# Sheet2.net
KiCad netlist of a schematic drawn in Altium Designer
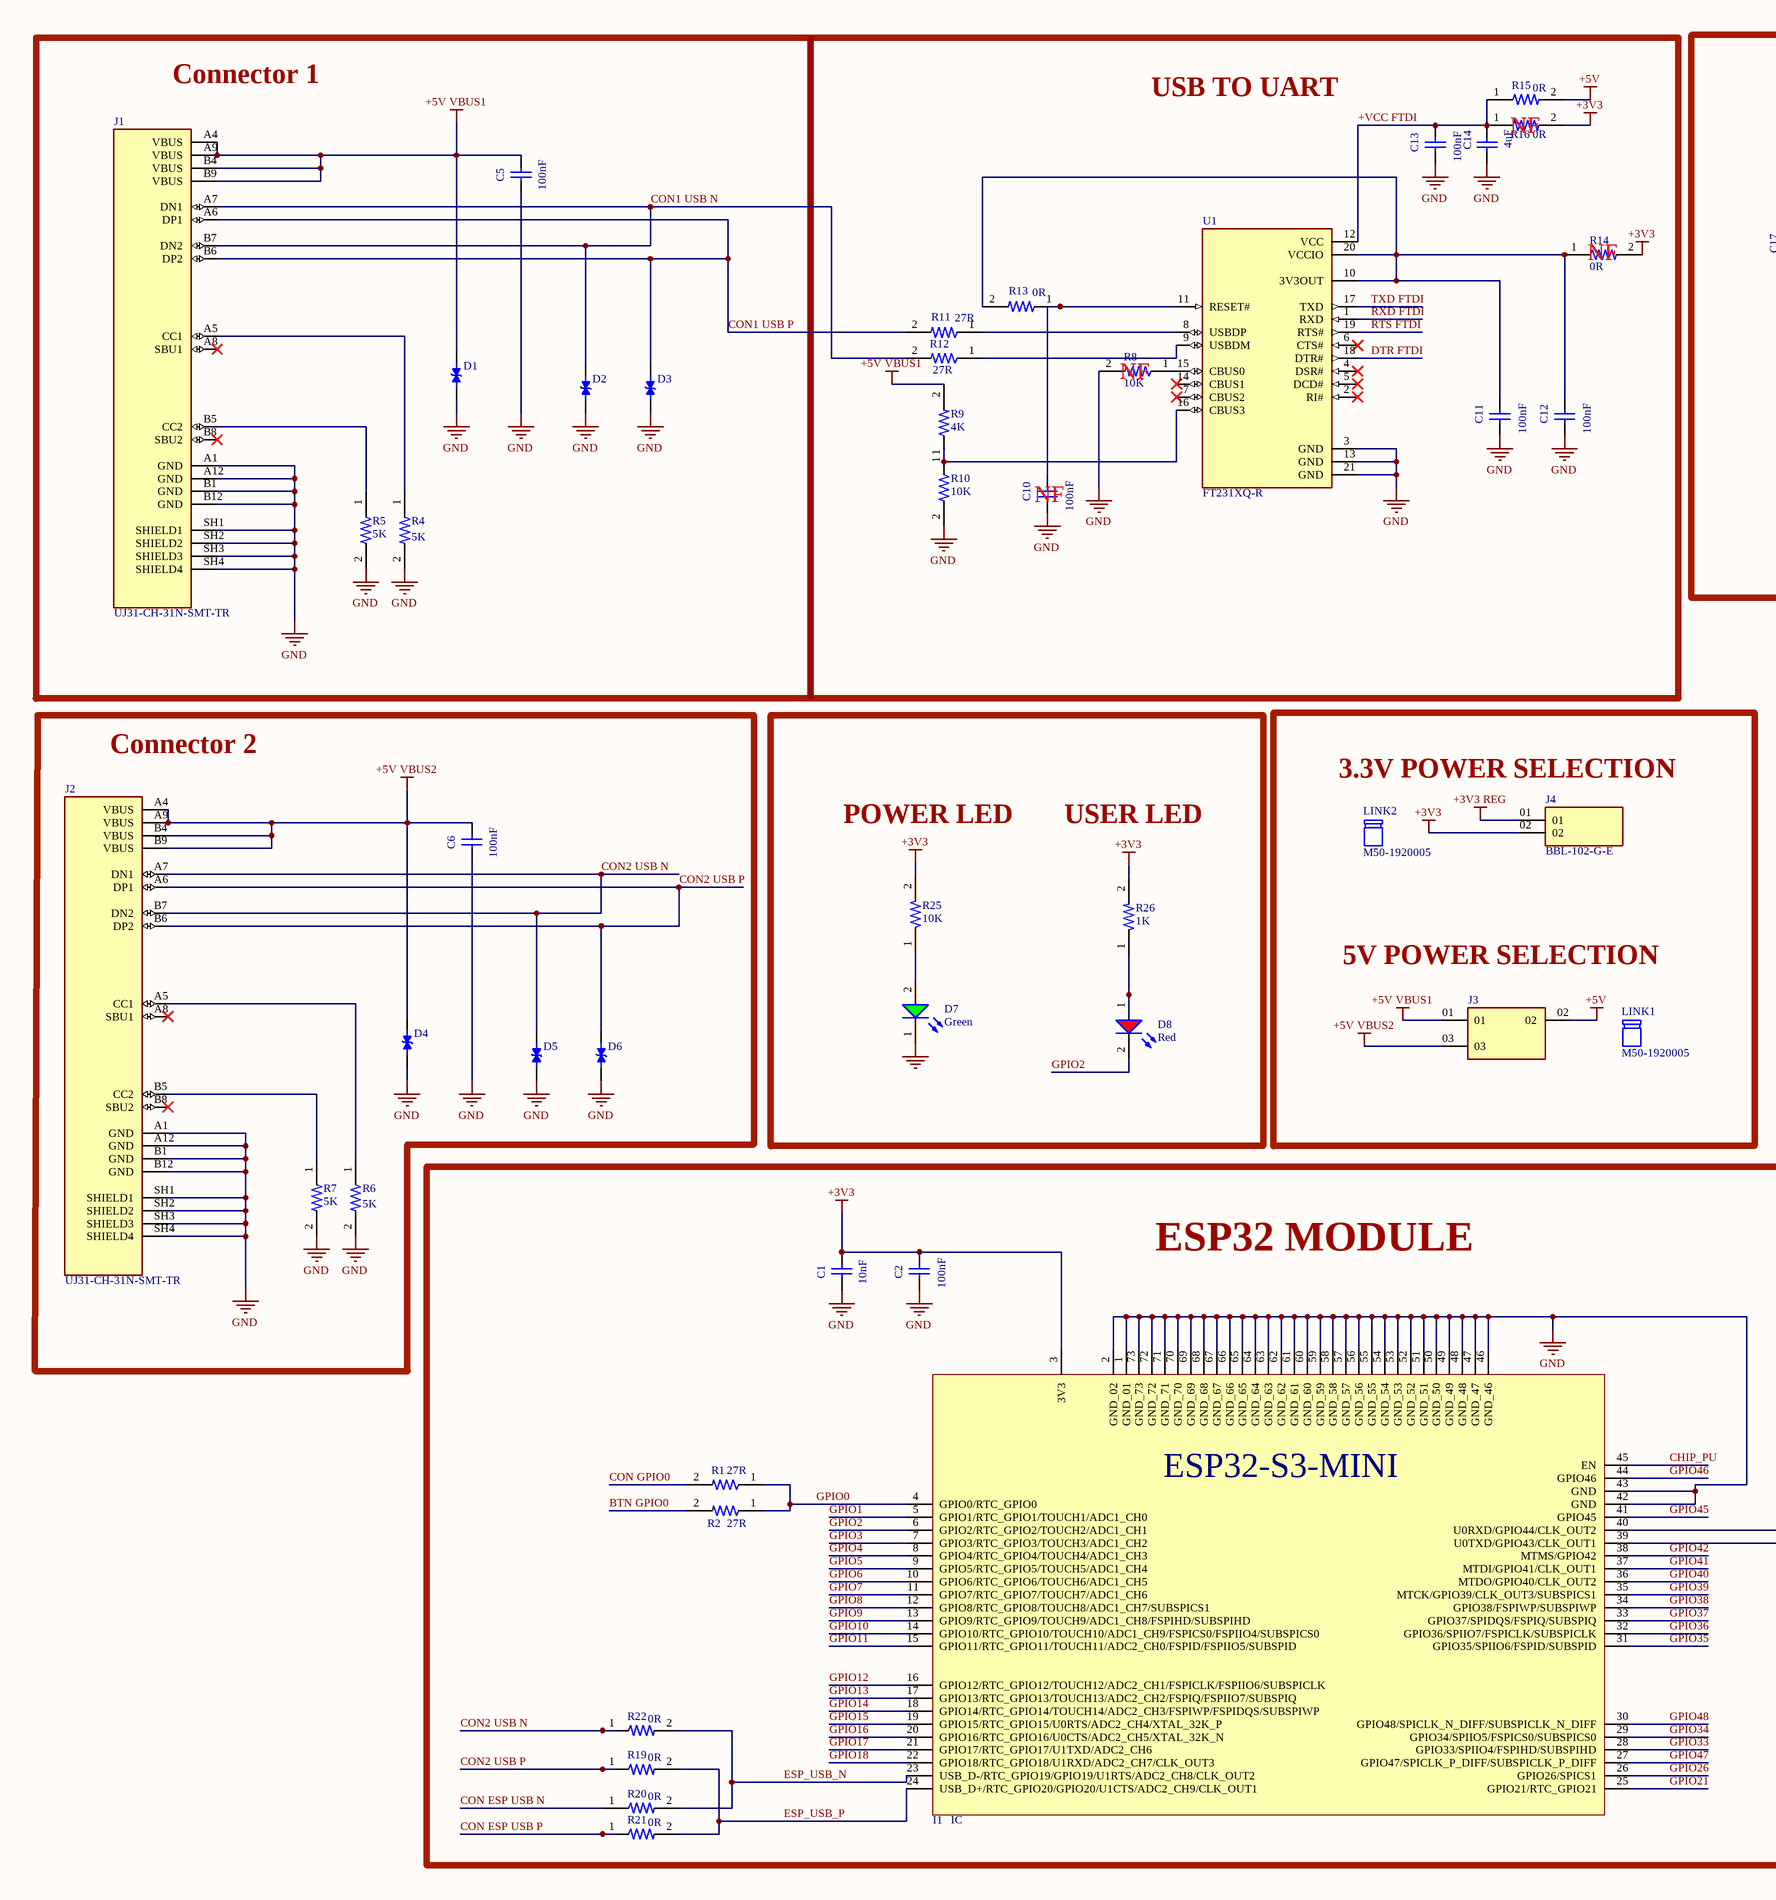
[diagram p0: Sheet2.SchDoc, left]
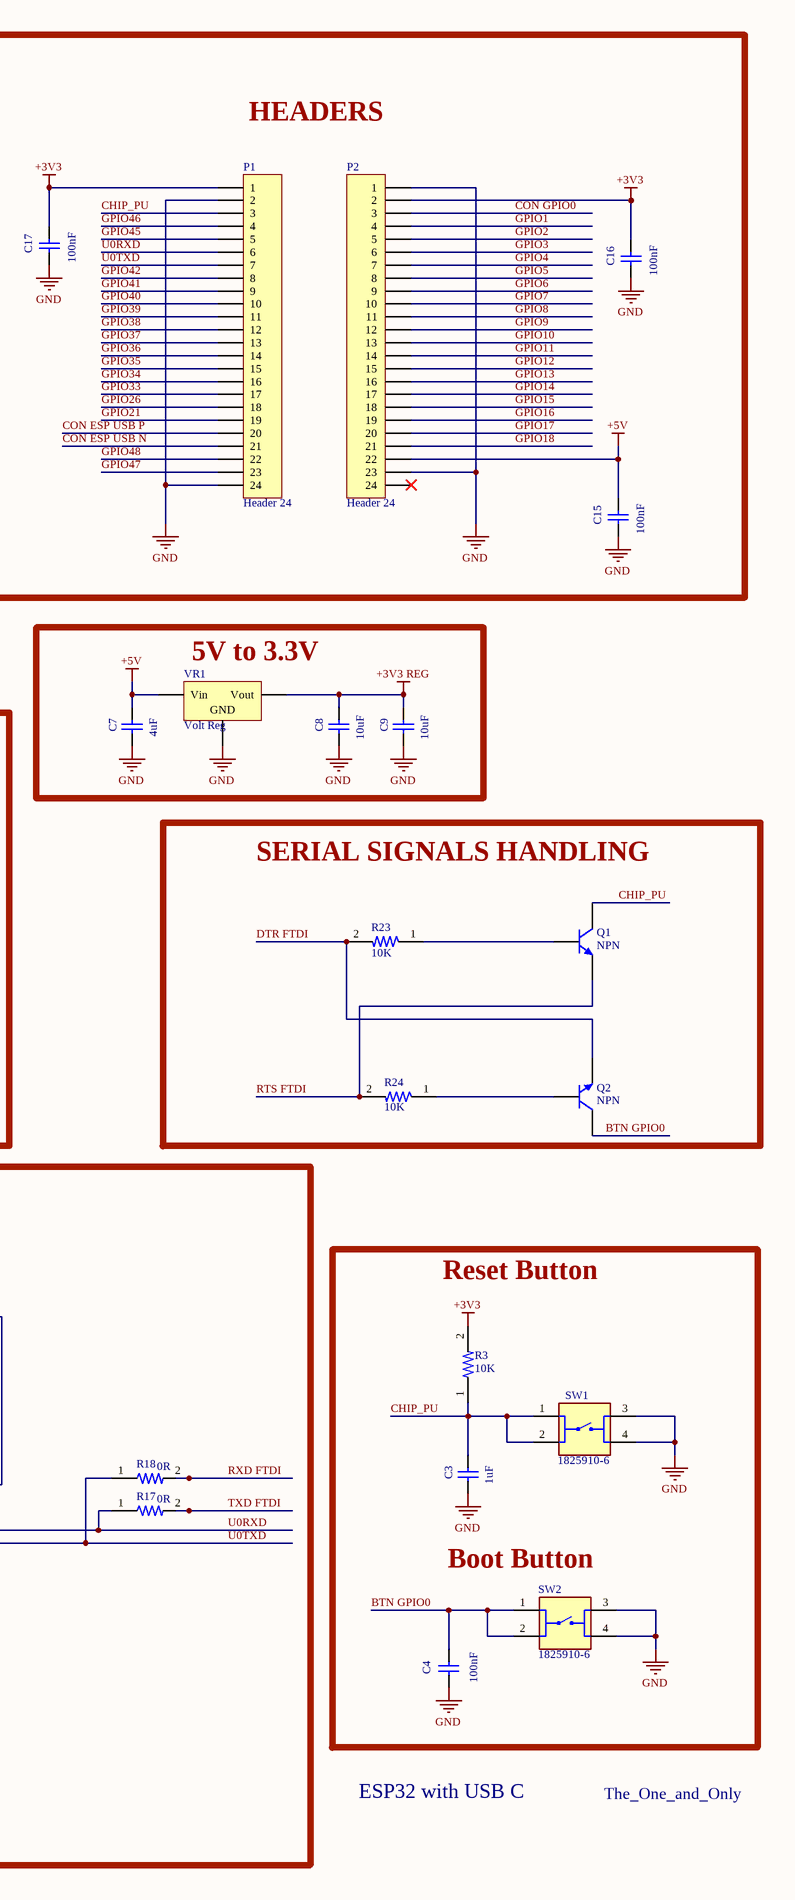
[diagram p1: Sheet2.SchDoc, right]

(export (version "E")
  (design (tool "Eeschema 10.0.6"))
  (components
    (comp (ref "C1")
      (value "10nF")
      (footprint "WCAP-CSGP_0603_L1.6W0.8H0.8_Reflow")
      (description "WCAP-CSGP Multilayer Ceramic Chip Capacitor, General Purpose, size 0603, X5R, 2.2μF, 16V")
      (fields
        (field (name "MANUFACTURER PART NUMBER") "885012106029")
        (field (name "MANUFACTURER") "Wurth Elektronik")
      )
      (libsource (lib "885012004001_Altium_WCAP-CSGP_rev24c") (part "885012106029"))
    )
    (comp (ref "C2")
      (value "100nF")
      (footprint "WCAP-CSGP_0603_L1.6W0.8H0.8_Reflow")
      (description "WCAP-CSGP Multilayer Ceramic Chip Capacitor, General Purpose, size 0603, X5R, 2.2μF, 16V")
      (fields
        (field (name "MANUFACTURER PART NUMBER") "885012106029")
        (field (name "MANUFACTURER") "Wurth Elektronik")
      )
      (libsource (lib "885012004001_Altium_WCAP-CSGP_rev24c") (part "885012106029"))
    )
    (comp (ref "C3")
      (value "1uF")
      (footprint "WCAP-CSGP_0603_L1.6W0.8H0.8_Reflow")
      (description "WCAP-CSGP Multilayer Ceramic Chip Capacitor, General Purpose, size 0603, X5R, 2.2μF, 16V")
      (fields
        (field (name "MANUFACTURER PART NUMBER") "885012106029")
        (field (name "MANUFACTURER") "Wurth Elektronik")
      )
      (libsource (lib "885012004001_Altium_WCAP-CSGP_rev24c") (part "885012106029"))
    )
    (comp (ref "C4")
      (value "100nF")
      (footprint "WCAP-CSGP_0603_L1.6W0.8H0.8_Reflow")
      (description "WCAP-CSGP Multilayer Ceramic Chip Capacitor, General Purpose, size 0603, X5R, 2.2μF, 16V")
      (fields
        (field (name "MANUFACTURER PART NUMBER") "885012106029")
        (field (name "MANUFACTURER") "Wurth Elektronik")
      )
      (libsource (lib "885012004001_Altium_WCAP-CSGP_rev24c") (part "885012106029"))
    )
    (comp (ref "C5")
      (value "100nF")
      (footprint "WCAP-CSGP_0603_L1.6W0.8H0.8_Reflow")
      (description "WCAP-CSGP Multilayer Ceramic Chip Capacitor, General Purpose, size 0603, X5R, 2.2μF, 16V")
      (fields
        (field (name "MANUFACTURER PART NUMBER") "885012106029")
        (field (name "MANUFACTURER") "Wurth Elektronik")
      )
      (libsource (lib "885012004001_Altium_WCAP-CSGP_rev24c") (part "885012106029"))
    )
    (comp (ref "C6")
      (value "100nF")
      (footprint "WCAP-CSGP_0603_L1.6W0.8H0.8_Reflow")
      (description "WCAP-CSGP Multilayer Ceramic Chip Capacitor, General Purpose, size 0603, X5R, 2.2μF, 16V")
      (fields
        (field (name "MANUFACTURER PART NUMBER") "885012106029")
        (field (name "MANUFACTURER") "Wurth Elektronik")
      )
      (libsource (lib "885012004001_Altium_WCAP-CSGP_rev24c") (part "885012106029"))
    )
    (comp (ref "C7")
      (value "4uF")
      (footprint "WCAP-CSGP_0603_L1.6W0.8H0.8_Reflow")
      (description "WCAP-CSGP Multilayer Ceramic Chip Capacitor, General Purpose, size 0603, X5R, 2.2μF, 16V")
      (fields
        (field (name "MANUFACTURER PART NUMBER") "885012106029")
        (field (name "MANUFACTURER") "Wurth Elektronik")
      )
      (libsource (lib "885012004001_Altium_WCAP-CSGP_rev24c") (part "885012106029"))
    )
    (comp (ref "C8")
      (value "10uF")
      (footprint "WCAP-CSGP_0603_L1.6W0.8H0.8_Reflow")
      (description "WCAP-CSGP Multilayer Ceramic Chip Capacitor, General Purpose, size 0603, X5R, 2.2μF, 16V")
      (fields
        (field (name "MANUFACTURER PART NUMBER") "885012106029")
        (field (name "MANUFACTURER") "Wurth Elektronik")
      )
      (libsource (lib "885012004001_Altium_WCAP-CSGP_rev24c") (part "885012106029"))
    )
    (comp (ref "C9")
      (value "10uF")
      (footprint "WCAP-CSGP_0603_L1.6W0.8H0.8_Reflow")
      (description "WCAP-CSGP Multilayer Ceramic Chip Capacitor, General Purpose, size 0603, X5R, 2.2μF, 16V")
      (fields
        (field (name "MANUFACTURER PART NUMBER") "885012106029")
        (field (name "MANUFACTURER") "Wurth Elektronik")
      )
      (libsource (lib "885012004001_Altium_WCAP-CSGP_rev24c") (part "885012106029"))
    )
    (comp (ref "C10")
      (value "100nF")
      (footprint "WCAP-CSGP_0603_L1.6W0.8H0.8_Reflow")
      (description "WCAP-CSGP Multilayer Ceramic Chip Capacitor, General Purpose, size 0603, X5R, 2.2μF, 16V")
      (fields
        (field (name "MANUFACTURER PART NUMBER") "885012106029")
        (field (name "MANUFACTURER") "Wurth Elektronik")
      )
      (libsource (lib "885012004001_Altium_WCAP-CSGP_rev24c") (part "885012106029"))
    )
    (comp (ref "C11")
      (value "100nF")
      (footprint "WCAP-CSGP_0603_L1.6W0.8H0.8_Reflow")
      (description "WCAP-CSGP Multilayer Ceramic Chip Capacitor, General Purpose, size 0603, X5R, 2.2μF, 16V")
      (fields
        (field (name "MANUFACTURER PART NUMBER") "885012106029")
        (field (name "MANUFACTURER") "Wurth Elektronik")
      )
      (libsource (lib "885012004001_Altium_WCAP-CSGP_rev24c") (part "885012106029"))
    )
    (comp (ref "C12")
      (value "100nF")
      (footprint "WCAP-CSGP_0603_L1.6W0.8H0.8_Reflow")
      (description "WCAP-CSGP Multilayer Ceramic Chip Capacitor, General Purpose, size 0603, X5R, 2.2μF, 16V")
      (fields
        (field (name "MANUFACTURER PART NUMBER") "885012106029")
        (field (name "MANUFACTURER") "Wurth Elektronik")
      )
      (libsource (lib "885012004001_Altium_WCAP-CSGP_rev24c") (part "885012106029"))
    )
    (comp (ref "C13")
      (value "100nF")
      (footprint "WCAP-CSGP_0603_L1.6W0.8H0.8_Reflow")
      (description "WCAP-CSGP Multilayer Ceramic Chip Capacitor, General Purpose, size 0603, X5R, 2.2μF, 16V")
      (fields
        (field (name "MANUFACTURER PART NUMBER") "885012106029")
        (field (name "MANUFACTURER") "Wurth Elektronik")
      )
      (libsource (lib "885012004001_Altium_WCAP-CSGP_rev24c") (part "885012106029"))
    )
    (comp (ref "C14")
      (value "4uF")
      (footprint "WCAP-CSGP_0603_L1.6W0.8H0.8_Reflow")
      (description "WCAP-CSGP Multilayer Ceramic Chip Capacitor, General Purpose, size 0603, X5R, 2.2μF, 16V")
      (fields
        (field (name "MANUFACTURER PART NUMBER") "885012106029")
        (field (name "MANUFACTURER") "Wurth Elektronik")
      )
      (libsource (lib "885012004001_Altium_WCAP-CSGP_rev24c") (part "885012106029"))
    )
    (comp (ref "C15")
      (value "100nF")
      (footprint "WCAP-CSGP_0603_L1.6W0.8H0.8_Reflow")
      (description "WCAP-CSGP Multilayer Ceramic Chip Capacitor, General Purpose, size 0603, X5R, 2.2μF, 16V")
      (fields
        (field (name "MANUFACTURER PART NUMBER") "885012106029")
        (field (name "MANUFACTURER") "Wurth Elektronik")
      )
      (libsource (lib "885012004001_Altium_WCAP-CSGP_rev24c") (part "885012106029"))
    )
    (comp (ref "C16")
      (value "100nF")
      (footprint "WCAP-CSGP_0603_L1.6W0.8H0.8_Reflow")
      (description "WCAP-CSGP Multilayer Ceramic Chip Capacitor, General Purpose, size 0603, X5R, 2.2μF, 16V")
      (fields
        (field (name "MANUFACTURER PART NUMBER") "885012106029")
        (field (name "MANUFACTURER") "Wurth Elektronik")
      )
      (libsource (lib "885012004001_Altium_WCAP-CSGP_rev24c") (part "885012106029"))
    )
    (comp (ref "C17")
      (value "100nF")
      (footprint "WCAP-CSGP_0603_L1.6W0.8H0.8_Reflow")
      (description "WCAP-CSGP Multilayer Ceramic Chip Capacitor, General Purpose, size 0603, X5R, 2.2μF, 16V")
      (fields
        (field (name "MANUFACTURER PART NUMBER") "885012106029")
        (field (name "MANUFACTURER") "Wurth Elektronik")
      )
      (libsource (lib "885012004001_Altium_WCAP-CSGP_rev24c") (part "885012106029"))
    )
    (comp (ref "D1")
      (value "TESDU12VRGG")
      (footprint "DIO_TESDU12VRGG")
      (description "33V Clamp 5A Ipp Tvs Diode Surface Mount 0603")
      (fields (field (name "MF") "Taiwan Semiconductor"))
      (libsource (lib "TESDU12VRGG") (part "TESDU12VRGG"))
    )
    (comp (ref "D2")
      (value "TESDU12VRGG")
      (footprint "DIO_TESDU12VRGG")
      (description "33V Clamp 5A Ipp Tvs Diode Surface Mount 0603")
      (fields (field (name "MF") "Taiwan Semiconductor"))
      (libsource (lib "TESDU12VRGG") (part "TESDU12VRGG"))
    )
    (comp (ref "D3")
      (value "TESDU12VRGG")
      (footprint "DIO_TESDU12VRGG")
      (description "33V Clamp 5A Ipp Tvs Diode Surface Mount 0603")
      (fields (field (name "MF") "Taiwan Semiconductor"))
      (libsource (lib "TESDU12VRGG") (part "TESDU12VRGG"))
    )
    (comp (ref "D4")
      (value "TESDU12VRGG")
      (footprint "DIO_TESDU12VRGG")
      (description "33V Clamp 5A Ipp Tvs Diode Surface Mount 0603")
      (fields (field (name "MF") "Taiwan Semiconductor"))
      (libsource (lib "TESDU12VRGG") (part "TESDU12VRGG"))
    )
    (comp (ref "D5")
      (value "TESDU12VRGG")
      (footprint "DIO_TESDU12VRGG")
      (description "33V Clamp 5A Ipp Tvs Diode Surface Mount 0603")
      (fields (field (name "MF") "Taiwan Semiconductor"))
      (libsource (lib "TESDU12VRGG") (part "TESDU12VRGG"))
    )
    (comp (ref "D6")
      (value "TESDU12VRGG")
      (footprint "DIO_TESDU12VRGG")
      (description "33V Clamp 5A Ipp Tvs Diode Surface Mount 0603")
      (fields (field (name "MF") "Taiwan Semiconductor"))
      (libsource (lib "TESDU12VRGG") (part "TESDU12VRGG"))
    )
    (comp (ref "D7")
      (value "Green")
      (footprint "WL-SMCW_0603_150060xx83000")
      (description "WL-SMCW Mono-color Chip LED Waterclear, SMT, size 0603, Green, 3.3V, 30°")
      (fields
        (field (name "MANUFACTURER PART NUMBER") "150060GS83000")
        (field (name "MANUFACTURER") "Wurth Elektronik")
      )
      (libsource (lib "150060AS75000_Altium_WL-SMCW_rev24b") (part "150060GS83000"))
    )
    (comp (ref "D8")
      (value "Red")
      (footprint "WL-SMCW_0603_150060xx75003")
      (description "WL-SMCW Mono-color Chip LED Waterclear, SMT, size 0603, Red, 2V, 140°")
      (fields
        (field (name "MANUFACTURER PART NUMBER") "150060RS75003")
        (field (name "MANUFACTURER") "Wurth Elektronik")
      )
      (libsource (lib "150060AS75000_Altium_WL-SMCW_rev24b") (part "150060RS75003"))
    )
    (comp (ref "I1")
      (value "IC")
      (footprint "XCVR_ESP32-MINI-1-N4")
      (libsource (lib "Schlib1") (part "Component_1"))
    )
    (comp (ref "J1")
      (value "UJ31-CH-31N-SMT-TR")
      (footprint "CUI_UJ31-CH-31N-SMT-TR")
      (description "Type C, USB 3.1 Gen 2, 5 A, Right Angle, Surface Mount (SMT), USB Receptacle")
      (fields (field (name "MF") "CUI Devices"))
      (libsource (lib "UJ31-CH-31N-SMT-TR") (part "UJ31-CH-31N-SMT-TR"))
    )
    (comp (ref "J2")
      (value "UJ31-CH-31N-SMT-TR")
      (footprint "CUI_UJ31-CH-31N-SMT-TR")
      (description "Type C, USB 3.1 Gen 2, 5 A, Right Angle, Surface Mount (SMT), USB Receptacle")
      (fields (field (name "MF") "CUI Devices"))
      (libsource (lib "UJ31-CH-31N-SMT-TR") (part "UJ31-CH-31N-SMT-TR"))
    )
    (comp (ref "J3")
      (value "TSW-101-23-S-T")
      (footprint "SAMTEC_TSW-101-23-S-T")
      (libsource (lib "TSW-101-23-S-T") (part "TSW-101-23-S-T"))
    )
    (comp (ref "J4")
      (value "BBL-102-G-E")
      (footprint "SAMTEC_BBL-102-G-E")
      (libsource (lib "BBL-102-G-E") (part "BBL-102-G-E"))
    )
    (comp (ref "LINK1")
      (value "M50-1920005")
      (description "CONN SHUNT 1.27MM RED")
      (fields (field (name "MANUFACTURER") "Harwin") (field (name "LCSC PART NUMBER") "C6985646"))
      (libsource (lib "Schlib") (part "M50-1920005"))
    )
    (comp (ref "LINK2")
      (value "M50-1920005")
      (description "CONN SHUNT 1.27MM RED")
      (fields (field (name "MANUFACTURER") "Harwin") (field (name "LCSC PART NUMBER") "C6985646"))
      (libsource (lib "Schlib") (part "M50-1920005"))
    )
    (comp (ref "P1")
      (value "Header 24")
      (footprint "HDR1X24")
      (description "Header, 24-Pin")
      (fields (field (name "PUBLISHER") "Altium Limited"))
      (libsource (lib "Miscellaneous Connectors") (part "Header 24"))
    )
    (comp (ref "P2")
      (value "Header 24")
      (footprint "HDR1X24")
      (description "Header, 24-Pin")
      (fields (field (name "PUBLISHER") "Altium Limited"))
      (libsource (lib "") (part "Header 24_1"))
    )
    (comp (ref "Q1")
      (value "NPN")
      (footprint "TO-226-AA")
      (description "NPN Bipolar Transistor")
      (fields (field (name "PUBLISHER") "Altium Limited"))
      (libsource (lib "Miscellaneous Devices") (part "NPN"))
    )
    (comp (ref "Q2")
      (value "NPN")
      (footprint "TO-226-AA")
      (description "NPN Bipolar Transistor")
      (fields (field (name "PUBLISHER") "Altium Limited"))
      (libsource (lib "Miscellaneous Devices") (part "NPN"))
    )
    (comp (ref "R1")
      (value "27R")
      (footprint "RESC1608X50N_CPF0603F10KC1")
      (description "Res Thin Film 0603 10K Ohm 1% 1/16W Â±50ppm/Â°C Molded SMD SMD Paper T/R")
      (fields (field (name "TOLERANCE") "1%") (field (name "MF") "TE Connectivity"))
      (libsource (lib "CPF0603F10KC1") (part "CPF0603F10KC1"))
    )
    (comp (ref "R2")
      (value "27R")
      (footprint "RESC1608X50N_CPF0603F10KC1")
      (description "Res Thin Film 0603 10K Ohm 1% 1/16W Â±50ppm/Â°C Molded SMD SMD Paper T/R")
      (fields (field (name "TOLERANCE") "1%") (field (name "MF") "TE Connectivity"))
      (libsource (lib "CPF0603F10KC1") (part "CPF0603F10KC1"))
    )
    (comp (ref "R3")
      (value "10K")
      (footprint "RESC1608X50N_CPF0603F10KC1")
      (description "Res Thin Film 0603 10K Ohm 1% 1/16W Â±50ppm/Â°C Molded SMD SMD Paper T/R")
      (fields (field (name "TOLERANCE") "1%") (field (name "MF") "TE Connectivity"))
      (libsource (lib "CPF0603F10KC1") (part "CPF0603F10KC1"))
    )
    (comp (ref "R4")
      (value "5K")
      (footprint "RESC1608X50N_CPF0603F10KC1")
      (description "Res Thin Film 0603 10K Ohm 1% 1/16W Â±50ppm/Â°C Molded SMD SMD Paper T/R")
      (fields (field (name "TOLERANCE") "1%") (field (name "MF") "TE Connectivity"))
      (libsource (lib "CPF0603F10KC1") (part "CPF0603F10KC1"))
    )
    (comp (ref "R5")
      (value "5K")
      (footprint "RESC1608X50N_CPF0603F10KC1")
      (description "Res Thin Film 0603 10K Ohm 1% 1/16W Â±50ppm/Â°C Molded SMD SMD Paper T/R")
      (fields (field (name "TOLERANCE") "1%") (field (name "MF") "TE Connectivity"))
      (libsource (lib "CPF0603F10KC1") (part "CPF0603F10KC1"))
    )
    (comp (ref "R6")
      (value "5K")
      (footprint "RESC1608X50N_CPF0603F10KC1")
      (description "Res Thin Film 0603 10K Ohm 1% 1/16W Â±50ppm/Â°C Molded SMD SMD Paper T/R")
      (fields (field (name "TOLERANCE") "1%") (field (name "MF") "TE Connectivity"))
      (libsource (lib "CPF0603F10KC1") (part "CPF0603F10KC1"))
    )
    (comp (ref "R7")
      (value "5K")
      (footprint "RESC1608X50N_CPF0603F10KC1")
      (description "Res Thin Film 0603 10K Ohm 1% 1/16W Â±50ppm/Â°C Molded SMD SMD Paper T/R")
      (fields (field (name "TOLERANCE") "1%") (field (name "MF") "TE Connectivity"))
      (libsource (lib "CPF0603F10KC1") (part "CPF0603F10KC1"))
    )
    (comp (ref "R8")
      (value "10K")
      (footprint "RESC1608X50N_CPF0603F10KC1")
      (description "Res Thin Film 0603 10K Ohm 1% 1/16W Â±50ppm/Â°C Molded SMD SMD Paper T/R")
      (fields (field (name "TOLERANCE") "1%") (field (name "MF") "TE Connectivity"))
      (libsource (lib "CPF0603F10KC1") (part "CPF0603F10KC1"))
    )
    (comp (ref "R9")
      (value "4K")
      (footprint "RESC1608X50N_CPF0603F10KC1")
      (description "Res Thin Film 0603 10K Ohm 1% 1/16W Â±50ppm/Â°C Molded SMD SMD Paper T/R")
      (fields (field (name "TOLERANCE") "1%") (field (name "MF") "TE Connectivity"))
      (libsource (lib "CPF0603F10KC1") (part "CPF0603F10KC1"))
    )
    (comp (ref "R10")
      (value "10K")
      (footprint "RESC1608X50N_CPF0603F10KC1")
      (description "Res Thin Film 0603 10K Ohm 1% 1/16W Â±50ppm/Â°C Molded SMD SMD Paper T/R")
      (fields (field (name "TOLERANCE") "1%") (field (name "MF") "TE Connectivity"))
      (libsource (lib "CPF0603F10KC1") (part "CPF0603F10KC1"))
    )
    (comp (ref "R11")
      (value "27R")
      (footprint "RESC1608X50N_CPF0603F10KC1")
      (description "Res Thin Film 0603 10K Ohm 1% 1/16W Â±50ppm/Â°C Molded SMD SMD Paper T/R")
      (fields (field (name "TOLERANCE") "1%") (field (name "MF") "TE Connectivity"))
      (libsource (lib "CPF0603F10KC1") (part "CPF0603F10KC1"))
    )
    (comp (ref "R12")
      (value "27R")
      (footprint "RESC1608X50N_CPF0603F10KC1")
      (description "Res Thin Film 0603 10K Ohm 1% 1/16W Â±50ppm/Â°C Molded SMD SMD Paper T/R")
      (fields (field (name "TOLERANCE") "1%") (field (name "MF") "TE Connectivity"))
      (libsource (lib "CPF0603F10KC1") (part "CPF0603F10KC1"))
    )
    (comp (ref "R13")
      (value "0R")
      (footprint "RESC1608X50N_CPF0603F10KC1")
      (description "Res Thin Film 0603 10K Ohm 1% 1/16W Â±50ppm/Â°C Molded SMD SMD Paper T/R")
      (fields (field (name "TOLERANCE") "1%") (field (name "MF") "TE Connectivity"))
      (libsource (lib "CPF0603F10KC1") (part "CPF0603F10KC1"))
    )
    (comp (ref "R14")
      (value "0R")
      (footprint "RESC1608X50N_CPF0603F10KC1")
      (description "Res Thin Film 0603 10K Ohm 1% 1/16W Â±50ppm/Â°C Molded SMD SMD Paper T/R")
      (fields (field (name "TOLERANCE") "1%") (field (name "MF") "TE Connectivity"))
      (libsource (lib "CPF0603F10KC1") (part "CPF0603F10KC1"))
    )
    (comp (ref "R15")
      (value "0R")
      (footprint "RESC1608X50N_CPF0603F10KC1")
      (description "Res Thin Film 0603 10K Ohm 1% 1/16W Â±50ppm/Â°C Molded SMD SMD Paper T/R")
      (fields (field (name "TOLERANCE") "1%") (field (name "MF") "TE Connectivity"))
      (libsource (lib "CPF0603F10KC1") (part "CPF0603F10KC1"))
    )
    (comp (ref "R16")
      (value "0R")
      (footprint "RESC1608X50N_CPF0603F10KC1")
      (description "Res Thin Film 0603 10K Ohm 1% 1/16W Â±50ppm/Â°C Molded SMD SMD Paper T/R")
      (fields (field (name "TOLERANCE") "1%") (field (name "MF") "TE Connectivity"))
      (libsource (lib "CPF0603F10KC1") (part "CPF0603F10KC1"))
    )
    (comp (ref "R17")
      (value "0R")
      (footprint "RESC1608X50N_CPF0603F10KC1")
      (description "Res Thin Film 0603 10K Ohm 1% 1/16W Â±50ppm/Â°C Molded SMD SMD Paper T/R")
      (fields (field (name "TOLERANCE") "1%") (field (name "MF") "TE Connectivity"))
      (libsource (lib "CPF0603F10KC1") (part "CPF0603F10KC1"))
    )
    (comp (ref "R18")
      (value "0R")
      (footprint "RESC1608X50N_CPF0603F10KC1")
      (description "Res Thin Film 0603 10K Ohm 1% 1/16W Â±50ppm/Â°C Molded SMD SMD Paper T/R")
      (fields (field (name "TOLERANCE") "1%") (field (name "MF") "TE Connectivity"))
      (libsource (lib "CPF0603F10KC1") (part "CPF0603F10KC1"))
    )
    (comp (ref "R19")
      (value "0R")
      (footprint "RESC1608X50N_CPF0603F10KC1")
      (description "Res Thin Film 0603 10K Ohm 1% 1/16W Â±50ppm/Â°C Molded SMD SMD Paper T/R")
      (fields (field (name "TOLERANCE") "1%") (field (name "MF") "TE Connectivity"))
      (libsource (lib "CPF0603F10KC1") (part "CPF0603F10KC1"))
    )
    (comp (ref "R20")
      (value "0R")
      (footprint "RESC1608X50N_CPF0603F10KC1")
      (description "Res Thin Film 0603 10K Ohm 1% 1/16W Â±50ppm/Â°C Molded SMD SMD Paper T/R")
      (fields (field (name "TOLERANCE") "1%") (field (name "MF") "TE Connectivity"))
      (libsource (lib "CPF0603F10KC1") (part "CPF0603F10KC1"))
    )
    (comp (ref "R21")
      (value "0R")
      (footprint "RESC1608X50N_CPF0603F10KC1")
      (description "Res Thin Film 0603 10K Ohm 1% 1/16W Â±50ppm/Â°C Molded SMD SMD Paper T/R")
      (fields (field (name "TOLERANCE") "1%") (field (name "MF") "TE Connectivity"))
      (libsource (lib "CPF0603F10KC1") (part "CPF0603F10KC1"))
    )
    (comp (ref "R22")
      (value "0R")
      (footprint "RESC1608X50N_CPF0603F10KC1")
      (description "Res Thin Film 0603 10K Ohm 1% 1/16W Â±50ppm/Â°C Molded SMD SMD Paper T/R")
      (fields (field (name "TOLERANCE") "1%") (field (name "MF") "TE Connectivity"))
      (libsource (lib "CPF0603F10KC1") (part "CPF0603F10KC1"))
    )
    (comp (ref "R23")
      (value "10K")
      (footprint "RESC1608X50N_CPF0603F10KC1")
      (description "Res Thin Film 0603 10K Ohm 1% 1/16W Â±50ppm/Â°C Molded SMD SMD Paper T/R")
      (fields (field (name "TOLERANCE") "1%") (field (name "MF") "TE Connectivity"))
      (libsource (lib "CPF0603F10KC1") (part "CPF0603F10KC1"))
    )
    (comp (ref "R24")
      (value "10K")
      (footprint "RESC1608X50N_CPF0603F10KC1")
      (description "Res Thin Film 0603 10K Ohm 1% 1/16W Â±50ppm/Â°C Molded SMD SMD Paper T/R")
      (fields (field (name "TOLERANCE") "1%") (field (name "MF") "TE Connectivity"))
      (libsource (lib "CPF0603F10KC1") (part "CPF0603F10KC1"))
    )
    (comp (ref "R25")
      (value "10K")
      (footprint "RESC1608X50N_CPF0603F10KC1")
      (description "Res Thin Film 0603 10K Ohm 1% 1/16W Â±50ppm/Â°C Molded SMD SMD Paper T/R")
      (fields (field (name "TOLERANCE") "1%") (field (name "MF") "TE Connectivity"))
      (libsource (lib "CPF0603F10KC1") (part "CPF0603F10KC1"))
    )
    (comp (ref "R26")
      (value "1K")
      (footprint "RESC1608X50N_CPF0603F10KC1")
      (description "Res Thin Film 0603 10K Ohm 1% 1/16W Â±50ppm/Â°C Molded SMD SMD Paper T/R")
      (fields (field (name "TOLERANCE") "1%") (field (name "MF") "TE Connectivity"))
      (libsource (lib "CPF0603F10KC1") (part "CPF0603F10KC1"))
    )
    (comp (ref "SW1")
      (value "1825910-6")
      (footprint "SW_1825910-6-4")
      (description "Switch Push Button OFF (ON) SPST Round Button 0.05A 24VDC Momentary Contact PC Pins Thru-Hole")
      (fields (field (name "MF") "TE Connectivity") (field (name "DIGI-KEY_PART_NUMBER") "450-1650-ND"))
      (libsource (lib "1825910-6") (part "1825910-6"))
    )
    (comp (ref "SW2")
      (value "1825910-6")
      (footprint "SW_1825910-6-4")
      (description "Switch Push Button OFF (ON) SPST Round Button 0.05A 24VDC Momentary Contact PC Pins Thru-Hole")
      (fields (field (name "MF") "TE Connectivity") (field (name "DIGI-KEY_PART_NUMBER") "450-1650-ND"))
      (libsource (lib "1825910-6") (part "1825910-6"))
    )
    (comp (ref "U1")
      (value "FT231XQ-R")
      (footprint "QFN50P400X400X80-21N")
      (description "USB2.0 Full Speed IC offers a compact bridge to full handshake UART Interface")
      (libsource (lib "FT231XQ-R") (part "FT231XQ-R"))
    )
    (comp (ref "VR1")
      (value "Volt Reg")
      (footprint "D2PAK_N")
      (description "Voltage Regulator")
      (fields (field (name "PUBLISHER") "Altium Limited"))
      (libsource (lib "Miscellaneous Devices") (part "Volt Reg"))
    )
  )
  (nets
    (net (code "1") (name "+3V3") (class "Default")
      (node (ref "C1") (pin "2") (pinfunction "2_2") (pintype "passive"))
      (node (ref "C16") (pin "2") (pinfunction "2_2") (pintype "passive"))
      (node (ref "C17") (pin "2") (pinfunction "2_2") (pintype "passive"))
      (node (ref "C2") (pin "2") (pinfunction "2_2") (pintype "passive"))
      (node (ref "I1") (pin "3") (pinfunction "3V3_3") (pintype "passive"))
      (node (ref "J4") (pin "02") (pinfunction "02_02") (pintype "passive"))
      (node (ref "P1") (pin "1") (pinfunction "1_1") (pintype "passive"))
      (node (ref "P2") (pin "2") (pinfunction "2_2") (pintype "passive"))
      (node (ref "R14") (pin "2") (pinfunction "2_2") (pintype "passive"))
      (node (ref "R16") (pin "2") (pinfunction "2_2") (pintype "passive"))
      (node (ref "R25") (pin "2") (pinfunction "2_2") (pintype "passive"))
      (node (ref "R26") (pin "2") (pinfunction "2_2") (pintype "passive"))
      (node (ref "R3") (pin "2") (pinfunction "2_2") (pintype "passive"))
    )
    (net (code "2") (name "+3V3 REG") (class "Default")
      (node (ref "C8") (pin "2") (pinfunction "2_2") (pintype "passive"))
      (node (ref "C9") (pin "2") (pinfunction "2_2") (pintype "passive"))
      (node (ref "J4") (pin "01") (pinfunction "01_01") (pintype "passive"))
      (node (ref "VR1") (pin "3") (pinfunction "Vout_3") (pintype "passive"))
    )
    (net (code "3") (name "+5V") (class "Default")
      (node (ref "C15") (pin "2") (pinfunction "2_2") (pintype "passive"))
      (node (ref "C7") (pin "2") (pinfunction "2_2") (pintype "passive"))
      (node (ref "J3") (pin "02") (pinfunction "02_02") (pintype "passive"))
      (node (ref "P2") (pin "22") (pinfunction "22_22") (pintype "passive"))
      (node (ref "R15") (pin "2") (pinfunction "2_2") (pintype "passive"))
      (node (ref "VR1") (pin "1") (pinfunction "Vin_1") (pintype "passive"))
    )
    (net (code "4") (name "+5V VBUS1") (class "Default")
      (node (ref "C5") (pin "2") (pinfunction "2_2") (pintype "passive"))
      (node (ref "D1") (pin "2") (pinfunction "2_2") (pintype "passive"))
      (node (ref "J1") (pin "A4") (pinfunction "VBUS_A4") (pintype "power_in"))
      (node (ref "J1") (pin "A9") (pinfunction "VBUS_A9") (pintype "power_in"))
      (node (ref "J1") (pin "B4") (pinfunction "VBUS_B4") (pintype "power_in"))
      (node (ref "J1") (pin "B9") (pinfunction "VBUS_B9") (pintype "power_in"))
      (node (ref "J3") (pin "01") (pinfunction "01_01") (pintype "passive"))
      (node (ref "R9") (pin "2") (pinfunction "2_2") (pintype "passive"))
    )
    (net (code "5") (name "+5V VBUS2") (class "Default")
      (node (ref "C6") (pin "2") (pinfunction "2_2") (pintype "passive"))
      (node (ref "D4") (pin "2") (pinfunction "2_2") (pintype "passive"))
      (node (ref "J2") (pin "A4") (pinfunction "VBUS_A4") (pintype "power_in"))
      (node (ref "J2") (pin "A9") (pinfunction "VBUS_A9") (pintype "power_in"))
      (node (ref "J2") (pin "B4") (pinfunction "VBUS_B4") (pintype "power_in"))
      (node (ref "J2") (pin "B9") (pinfunction "VBUS_B9") (pintype "power_in"))
      (node (ref "J3") (pin "03") (pinfunction "03_03") (pintype "passive"))
    )
    (net (code "6") (name "/+VCC FTDI") (class "Default")
      (node (ref "C13") (pin "2") (pinfunction "2_2") (pintype "passive"))
      (node (ref "C14") (pin "2") (pinfunction "2_2") (pintype "passive"))
      (node (ref "R15") (pin "1") (pinfunction "1_1") (pintype "passive"))
      (node (ref "R16") (pin "1") (pinfunction "1_1") (pintype "passive"))
      (node (ref "U1") (pin "12") (pinfunction "VCC_12") (pintype "power_in"))
    )
    (net (code "7") (name "/BTN GPIO0") (class "Default")
      (node (ref "C4") (pin "2") (pinfunction "2_2") (pintype "passive"))
      (node (ref "Q2") (pin "1") (pinfunction "C_1") (pintype "passive"))
      (node (ref "R2") (pin "2") (pinfunction "2_2") (pintype "passive"))
      (node (ref "SW2") (pin "1") (pinfunction "1_1") (pintype "passive"))
      (node (ref "SW2") (pin "2") (pinfunction "2_2") (pintype "passive"))
    )
    (net (code "8") (name "/CHIP_PU") (class "Default")
      (node (ref "C3") (pin "2") (pinfunction "2_2") (pintype "passive"))
      (node (ref "I1") (pin "45") (pinfunction "EN_45") (pintype "passive"))
      (node (ref "P1") (pin "3") (pinfunction "3_3") (pintype "passive"))
      (node (ref "Q1") (pin "1") (pinfunction "C_1") (pintype "passive"))
      (node (ref "R3") (pin "1") (pinfunction "1_1") (pintype "passive"))
      (node (ref "SW1") (pin "1") (pinfunction "1_1") (pintype "passive"))
      (node (ref "SW1") (pin "2") (pinfunction "2_2") (pintype "passive"))
    )
    (net (code "9") (name "/CON ESP USB N") (class "Default")
      (node (ref "P1") (pin "21") (pinfunction "21_21") (pintype "passive"))
      (node (ref "R20") (pin "1") (pinfunction "1_1") (pintype "passive"))
    )
    (net (code "10") (name "/CON ESP USB P") (class "Default")
      (node (ref "P1") (pin "20") (pinfunction "20_20") (pintype "passive"))
      (node (ref "R21") (pin "1") (pinfunction "1_1") (pintype "passive"))
    )
    (net (code "11") (name "/CON GPIO0") (class "Default")
      (node (ref "P2") (pin "3") (pinfunction "3_3") (pintype "passive"))
      (node (ref "R1") (pin "2") (pinfunction "2_2") (pintype "passive"))
    )
    (net (code "12") (name "/CON1 USB N") (class "Default")
      (node (ref "D2") (pin "2") (pinfunction "2_2") (pintype "passive"))
      (node (ref "J1") (pin "A7") (pinfunction "DN1_A7") (pintype "bidirectional"))
      (node (ref "J1") (pin "B7") (pinfunction "DN2_B7") (pintype "bidirectional"))
      (node (ref "R12") (pin "2") (pinfunction "2_2") (pintype "passive"))
    )
    (net (code "13") (name "/CON1 USB P") (class "Default")
      (node (ref "D3") (pin "2") (pinfunction "2_2") (pintype "passive"))
      (node (ref "J1") (pin "A6") (pinfunction "DP1_A6") (pintype "bidirectional"))
      (node (ref "J1") (pin "B6") (pinfunction "DP2_B6") (pintype "bidirectional"))
      (node (ref "R11") (pin "2") (pinfunction "2_2") (pintype "passive"))
    )
    (net (code "14") (name "/CON2 USB N") (class "Default")
      (node (ref "D5") (pin "2") (pinfunction "2_2") (pintype "passive"))
      (node (ref "J2") (pin "A7") (pinfunction "DN1_A7") (pintype "bidirectional"))
      (node (ref "J2") (pin "B7") (pinfunction "DN2_B7") (pintype "bidirectional"))
      (node (ref "R22") (pin "1") (pinfunction "1_1") (pintype "passive"))
    )
    (net (code "15") (name "/CON2 USB P") (class "Default")
      (node (ref "D6") (pin "2") (pinfunction "2_2") (pintype "passive"))
      (node (ref "J2") (pin "A6") (pinfunction "DP1_A6") (pintype "bidirectional"))
      (node (ref "J2") (pin "B6") (pinfunction "DP2_B6") (pintype "bidirectional"))
      (node (ref "R19") (pin "1") (pinfunction "1_1") (pintype "passive"))
    )
    (net (code "16") (name "/DTR FTDI") (class "Default")
      (node (ref "Q2") (pin "3") (pinfunction "E_3") (pintype "passive"))
      (node (ref "R23") (pin "2") (pinfunction "2_2") (pintype "passive"))
      (node (ref "U1") (pin "18") (pinfunction "DTR#_18") (pintype "output"))
    )
    (net (code "17") (name "/ESP_USB_N") (class "Default")
      (node (ref "I1") (pin "23") (pinfunction "USB_D-/RTC_GPIO19/GPIO19/U1RTS/ADC2_CH8/CLK_OUT2_23") (pintype "passive"))
      (node (ref "R20") (pin "2") (pinfunction "2_2") (pintype "passive"))
      (node (ref "R22") (pin "2") (pinfunction "2_2") (pintype "passive"))
    )
    (net (code "18") (name "/ESP_USB_P") (class "Default")
      (node (ref "I1") (pin "24") (pinfunction "USB_D+/RTC_GPIO20/GPIO20/U1CTS/ADC2_CH9/CLK_OUT1_24") (pintype "passive"))
      (node (ref "R19") (pin "2") (pinfunction "2_2") (pintype "passive"))
      (node (ref "R21") (pin "2") (pinfunction "2_2") (pintype "passive"))
    )
    (net (code "19") (name "/GPIO0") (class "Default")
      (node (ref "I1") (pin "4") (pinfunction "GPIO0/RTC_GPIO0_4") (pintype "passive"))
      (node (ref "R1") (pin "1") (pinfunction "1_1") (pintype "passive"))
      (node (ref "R2") (pin "1") (pinfunction "1_1") (pintype "passive"))
    )
    (net (code "20") (name "/GPIO1") (class "Default")
      (node (ref "I1") (pin "5") (pinfunction "GPIO1/RTC_GPIO1/TOUCH1/ADC1_CH0_5") (pintype "passive"))
      (node (ref "P2") (pin "4") (pinfunction "4_4") (pintype "passive"))
    )
    (net (code "21") (name "/GPIO2") (class "Default")
      (node (ref "D8") (pin "2") (pinfunction "K_2") (pintype "passive"))
      (node (ref "I1") (pin "6") (pinfunction "GPIO2/RTC_GPIO2/TOUCH2/ADC1_CH1_6") (pintype "passive"))
      (node (ref "P2") (pin "5") (pinfunction "5_5") (pintype "passive"))
    )
    (net (code "22") (name "/GPIO3") (class "Default")
      (node (ref "I1") (pin "7") (pinfunction "GPIO3/RTC_GPIO3/TOUCH3/ADC1_CH2_7") (pintype "passive"))
      (node (ref "P2") (pin "6") (pinfunction "6_6") (pintype "passive"))
    )
    (net (code "23") (name "/GPIO4") (class "Default")
      (node (ref "I1") (pin "8") (pinfunction "GPIO4/RTC_GPIO4/TOUCH4/ADC1_CH3_8") (pintype "passive"))
      (node (ref "P2") (pin "7") (pinfunction "7_7") (pintype "passive"))
    )
    (net (code "24") (name "/GPIO5") (class "Default")
      (node (ref "I1") (pin "9") (pinfunction "GPIO5/RTC_GPIO5/TOUCH5/ADC1_CH4_9") (pintype "passive"))
      (node (ref "P2") (pin "8") (pinfunction "8_8") (pintype "passive"))
    )
    (net (code "25") (name "/GPIO6") (class "Default")
      (node (ref "I1") (pin "10") (pinfunction "GPIO6/RTC_GPIO6/TOUCH6/ADC1_CH5_10") (pintype "passive"))
      (node (ref "P2") (pin "9") (pinfunction "9_9") (pintype "passive"))
    )
    (net (code "26") (name "/GPIO7") (class "Default")
      (node (ref "I1") (pin "11") (pinfunction "GPIO7/RTC_GPIO7/TOUCH7/ADC1_CH6_11") (pintype "passive"))
      (node (ref "P2") (pin "10") (pinfunction "10_10") (pintype "passive"))
    )
    (net (code "27") (name "/GPIO8") (class "Default")
      (node (ref "I1") (pin "12") (pinfunction "GPIO8/RTC_GPIO8/TOUCH8/ADC1_CH7/SUBSPICS1_12") (pintype "passive"))
      (node (ref "P2") (pin "11") (pinfunction "11_11") (pintype "passive"))
    )
    (net (code "28") (name "/GPIO9") (class "Default")
      (node (ref "I1") (pin "13") (pinfunction "GPIO9/RTC_GPIO9/TOUCH9/ADC1_CH8/FSPIHD/SUBSPIHD_13") (pintype "passive"))
      (node (ref "P2") (pin "12") (pinfunction "12_12") (pintype "passive"))
    )
    (net (code "29") (name "/GPIO10") (class "Default")
      (node (ref "I1") (pin "14") (pinfunction "GPIO10/RTC_GPIO10/TOUCH10/ADC1_CH9/FSPICS0/FSPIIO4/SUBSPICS0_14") (pintype "passive"))
      (node (ref "P2") (pin "13") (pinfunction "13_13") (pintype "passive"))
    )
    (net (code "30") (name "/GPIO11") (class "Default")
      (node (ref "I1") (pin "15") (pinfunction "GPIO11/RTC_GPIO11/TOUCH11/ADC2_CH0/FSPID/FSPIIO5/SUBSPID_15") (pintype "passive"))
      (node (ref "P2") (pin "14") (pinfunction "14_14") (pintype "passive"))
    )
    (net (code "31") (name "/GPIO12") (class "Default")
      (node (ref "I1") (pin "16") (pinfunction "GPIO12/RTC_GPIO12/TOUCH12/ADC2_CH1/FSPICLK/FSPIIO6/SUBSPICLK_16") (pintype "passive"))
      (node (ref "P2") (pin "15") (pinfunction "15_15") (pintype "passive"))
    )
    (net (code "32") (name "/GPIO13") (class "Default")
      (node (ref "I1") (pin "17") (pinfunction "GPIO13/RTC_GPIO13/TOUCH13/ADC2_CH2/FSPIQ/FSPIIO7/SUBSPIQ_17") (pintype "passive"))
      (node (ref "P2") (pin "16") (pinfunction "16_16") (pintype "passive"))
    )
    (net (code "33") (name "/GPIO14") (class "Default")
      (node (ref "I1") (pin "18") (pinfunction "GPIO14/RTC_GPIO14/TOUCH14/ADC2_CH3/FSPIWP/FSPIDQS/SUBSPIWP_18") (pintype "passive"))
      (node (ref "P2") (pin "17") (pinfunction "17_17") (pintype "passive"))
    )
    (net (code "34") (name "/GPIO15") (class "Default")
      (node (ref "I1") (pin "19") (pinfunction "GPIO15/RTC_GPIO15/U0RTS/ADC2_CH4/XTAL_32K_P_19") (pintype "passive"))
      (node (ref "P2") (pin "18") (pinfunction "18_18") (pintype "passive"))
    )
    (net (code "35") (name "/GPIO16") (class "Default")
      (node (ref "I1") (pin "20") (pinfunction "GPIO16/RTC_GPIO16/U0CTS/ADC2_CH5/XTAL_32K_N_20") (pintype "passive"))
      (node (ref "P2") (pin "19") (pinfunction "19_19") (pintype "passive"))
    )
    (net (code "36") (name "/GPIO17") (class "Default")
      (node (ref "I1") (pin "21") (pinfunction "GPIO17/RTC_GPIO17/U1TXD/ADC2_CH6_21") (pintype "passive"))
      (node (ref "P2") (pin "20") (pinfunction "20_20") (pintype "passive"))
    )
    (net (code "37") (name "/GPIO18") (class "Default")
      (node (ref "I1") (pin "22") (pinfunction "GPIO18/RTC_GPIO18/U1RXD/ADC2_CH7/CLK_OUT3_22") (pintype "passive"))
      (node (ref "P2") (pin "21") (pinfunction "21_21") (pintype "passive"))
    )
    (net (code "38") (name "/GPIO21") (class "Default")
      (node (ref "I1") (pin "25") (pinfunction "GPIO21/RTC_GPIO21_25") (pintype "passive"))
      (node (ref "P1") (pin "19") (pinfunction "19_19") (pintype "passive"))
    )
    (net (code "39") (name "/GPIO26") (class "Default")
      (node (ref "I1") (pin "26") (pinfunction "GPIO26/SPICS1_26") (pintype "passive"))
      (node (ref "P1") (pin "18") (pinfunction "18_18") (pintype "passive"))
    )
    (net (code "40") (name "/GPIO33") (class "Default")
      (node (ref "I1") (pin "28") (pinfunction "GPIO33/SPIIO4/FSPIHD/SUBSPIHD_28") (pintype "passive"))
      (node (ref "P1") (pin "17") (pinfunction "17_17") (pintype "passive"))
    )
    (net (code "41") (name "/GPIO34") (class "Default")
      (node (ref "I1") (pin "29") (pinfunction "GPIO34/SPIIO5/FSPICS0/SUBSPICS0_29") (pintype "passive"))
      (node (ref "P1") (pin "16") (pinfunction "16_16") (pintype "passive"))
    )
    (net (code "42") (name "/GPIO35") (class "Default")
      (node (ref "I1") (pin "31") (pinfunction "GPIO35/SPIIO6/FSPID/SUBSPID_31") (pintype "passive"))
      (node (ref "P1") (pin "15") (pinfunction "15_15") (pintype "passive"))
    )
    (net (code "43") (name "/GPIO36") (class "Default")
      (node (ref "I1") (pin "32") (pinfunction "GPIO36/SPIIO7/FSPICLK/SUBSPICLK_32") (pintype "passive"))
      (node (ref "P1") (pin "14") (pinfunction "14_14") (pintype "passive"))
    )
    (net (code "44") (name "/GPIO37") (class "Default")
      (node (ref "I1") (pin "33") (pinfunction "GPIO37/SPIDQS/FSPIQ/SUBSPIQ_33") (pintype "passive"))
      (node (ref "P1") (pin "13") (pinfunction "13_13") (pintype "passive"))
    )
    (net (code "45") (name "/GPIO38") (class "Default")
      (node (ref "I1") (pin "34") (pinfunction "GPIO38/FSPIWP/SUBSPIWP_34") (pintype "passive"))
      (node (ref "P1") (pin "12") (pinfunction "12_12") (pintype "passive"))
    )
    (net (code "46") (name "/GPIO39") (class "Default")
      (node (ref "I1") (pin "35") (pinfunction "MTCK/GPIO39/CLK_OUT3/SUBSPICS1_35") (pintype "passive"))
      (node (ref "P1") (pin "11") (pinfunction "11_11") (pintype "passive"))
    )
    (net (code "47") (name "/GPIO40") (class "Default")
      (node (ref "I1") (pin "36") (pinfunction "MTDO/GPIO40/CLK_OUT2_36") (pintype "passive"))
      (node (ref "P1") (pin "10") (pinfunction "10_10") (pintype "passive"))
    )
    (net (code "48") (name "/GPIO41") (class "Default")
      (node (ref "I1") (pin "37") (pinfunction "MTDI/GPIO41/CLK_OUT1_37") (pintype "passive"))
      (node (ref "P1") (pin "9") (pinfunction "9_9") (pintype "passive"))
    )
    (net (code "49") (name "/GPIO42") (class "Default")
      (node (ref "I1") (pin "38") (pinfunction "MTMS/GPIO42_38") (pintype "passive"))
      (node (ref "P1") (pin "8") (pinfunction "8_8") (pintype "passive"))
    )
    (net (code "50") (name "/GPIO45") (class "Default")
      (node (ref "I1") (pin "41") (pinfunction "GPIO45_41") (pintype "passive"))
      (node (ref "P1") (pin "5") (pinfunction "5_5") (pintype "passive"))
    )
    (net (code "51") (name "/GPIO46") (class "Default")
      (node (ref "I1") (pin "44") (pinfunction "GPIO46_44") (pintype "passive"))
      (node (ref "P1") (pin "4") (pinfunction "4_4") (pintype "passive"))
    )
    (net (code "52") (name "/GPIO47") (class "Default")
      (node (ref "I1") (pin "27") (pinfunction "GPIO47/SPICLK_P_DIFF/SUBSPICLK_P_DIFF_27") (pintype "passive"))
      (node (ref "P1") (pin "23") (pinfunction "23_23") (pintype "passive"))
    )
    (net (code "53") (name "/GPIO48") (class "Default")
      (node (ref "I1") (pin "30") (pinfunction "GPIO48/SPICLK_N_DIFF/SUBSPICLK_N_DIFF_30") (pintype "passive"))
      (node (ref "P1") (pin "22") (pinfunction "22_22") (pintype "passive"))
    )
    (net (code "54") (name "/RTS FTDI") (class "Default")
      (node (ref "Q1") (pin "3") (pinfunction "E_3") (pintype "passive"))
      (node (ref "R24") (pin "2") (pinfunction "2_2") (pintype "passive"))
      (node (ref "U1") (pin "19") (pinfunction "RTS#_19") (pintype "output"))
    )
    (net (code "55") (name "/RXD FTDI") (class "Default")
      (node (ref "R18") (pin "2") (pinfunction "2_2") (pintype "passive"))
      (node (ref "U1") (pin "1") (pinfunction "RXD_1") (pintype "input"))
    )
    (net (code "56") (name "/TXD FTDI") (class "Default")
      (node (ref "R17") (pin "2") (pinfunction "2_2") (pintype "passive"))
      (node (ref "U1") (pin "17") (pinfunction "TXD_17") (pintype "output"))
    )
    (net (code "57") (name "/U0RXD") (class "Default")
      (node (ref "I1") (pin "40") (pinfunction "U0RXD/GPIO44/CLK_OUT2_40") (pintype "passive"))
      (node (ref "P1") (pin "6") (pinfunction "6_6") (pintype "passive"))
      (node (ref "R17") (pin "1") (pinfunction "1_1") (pintype "passive"))
    )
    (net (code "58") (name "/U0TXD") (class "Default")
      (node (ref "I1") (pin "39") (pinfunction "U0TXD/GPIO43/CLK_OUT1_39") (pintype "passive"))
      (node (ref "P1") (pin "7") (pinfunction "7_7") (pintype "passive"))
      (node (ref "R18") (pin "1") (pinfunction "1_1") (pintype "passive"))
    )
    (net (code "59") (name "GND") (class "Default")
      (node (ref "C1") (pin "1") (pinfunction "1_1") (pintype "passive"))
      (node (ref "C10") (pin "1") (pinfunction "1_1") (pintype "passive"))
      (node (ref "C11") (pin "1") (pinfunction "1_1") (pintype "passive"))
      (node (ref "C12") (pin "1") (pinfunction "1_1") (pintype "passive"))
      (node (ref "C13") (pin "1") (pinfunction "1_1") (pintype "passive"))
      (node (ref "C14") (pin "1") (pinfunction "1_1") (pintype "passive"))
      (node (ref "C15") (pin "1") (pinfunction "1_1") (pintype "passive"))
      (node (ref "C16") (pin "1") (pinfunction "1_1") (pintype "passive"))
      (node (ref "C17") (pin "1") (pinfunction "1_1") (pintype "passive"))
      (node (ref "C2") (pin "1") (pinfunction "1_1") (pintype "passive"))
      (node (ref "C3") (pin "1") (pinfunction "1_1") (pintype "passive"))
      (node (ref "C4") (pin "1") (pinfunction "1_1") (pintype "passive"))
      (node (ref "C5") (pin "1") (pinfunction "1_1") (pintype "passive"))
      (node (ref "C6") (pin "1") (pinfunction "1_1") (pintype "passive"))
      (node (ref "C7") (pin "1") (pinfunction "1_1") (pintype "passive"))
      (node (ref "C8") (pin "1") (pinfunction "1_1") (pintype "passive"))
      (node (ref "C9") (pin "1") (pinfunction "1_1") (pintype "passive"))
      (node (ref "D1") (pin "1") (pinfunction "1_1") (pintype "passive"))
      (node (ref "D2") (pin "1") (pinfunction "1_1") (pintype "passive"))
      (node (ref "D3") (pin "1") (pinfunction "1_1") (pintype "passive"))
      (node (ref "D4") (pin "1") (pinfunction "1_1") (pintype "passive"))
      (node (ref "D5") (pin "1") (pinfunction "1_1") (pintype "passive"))
      (node (ref "D6") (pin "1") (pinfunction "1_1") (pintype "passive"))
      (node (ref "D7") (pin "1") (pinfunction "K_1") (pintype "passive"))
      (node (ref "I1") (pin "1") (pinfunction "GND_01_1") (pintype "passive"))
      (node (ref "I1") (pin "2") (pinfunction "GND_02_2") (pintype "passive"))
      (node (ref "I1") (pin "42") (pinfunction "GND_42") (pintype "passive"))
      (node (ref "I1") (pin "43") (pinfunction "GND_43") (pintype "passive"))
      (node (ref "I1") (pin "46") (pinfunction "GND_46_46") (pintype "passive"))
      (node (ref "I1") (pin "47") (pinfunction "GND_47_47") (pintype "passive"))
      (node (ref "I1") (pin "48") (pinfunction "GND_48_48") (pintype "passive"))
      (node (ref "I1") (pin "49") (pinfunction "GND_49_49") (pintype "passive"))
      (node (ref "I1") (pin "50") (pinfunction "GND_50_50") (pintype "passive"))
      (node (ref "I1") (pin "51") (pinfunction "GND_51_51") (pintype "passive"))
      (node (ref "I1") (pin "52") (pinfunction "GND_52_52") (pintype "passive"))
      (node (ref "I1") (pin "53") (pinfunction "GND_53_53") (pintype "passive"))
      (node (ref "I1") (pin "54") (pinfunction "GND_54_54") (pintype "passive"))
      (node (ref "I1") (pin "55") (pinfunction "GND_55_55") (pintype "passive"))
      (node (ref "I1") (pin "56") (pinfunction "GND_56_56") (pintype "passive"))
      (node (ref "I1") (pin "57") (pinfunction "GND_57_57") (pintype "passive"))
      (node (ref "I1") (pin "58") (pinfunction "GND_58_58") (pintype "passive"))
      (node (ref "I1") (pin "59") (pinfunction "GND_59_59") (pintype "passive"))
      (node (ref "I1") (pin "60") (pinfunction "GND_60_60") (pintype "passive"))
      (node (ref "I1") (pin "61") (pinfunction "GND_61_61") (pintype "passive"))
      (node (ref "I1") (pin "62") (pinfunction "GND_62_62") (pintype "passive"))
      (node (ref "I1") (pin "63") (pinfunction "GND_63_63") (pintype "passive"))
      (node (ref "I1") (pin "64") (pinfunction "GND_64_64") (pintype "passive"))
      (node (ref "I1") (pin "65") (pinfunction "GND_65_65") (pintype "passive"))
      (node (ref "I1") (pin "66") (pinfunction "GND_66_66") (pintype "passive"))
      (node (ref "I1") (pin "67") (pinfunction "GND_67_67") (pintype "passive"))
      (node (ref "I1") (pin "68") (pinfunction "GND_68_68") (pintype "passive"))
      (node (ref "I1") (pin "69") (pinfunction "GND_69_69") (pintype "passive"))
      (node (ref "I1") (pin "70") (pinfunction "GND_70_70") (pintype "passive"))
      (node (ref "I1") (pin "71") (pinfunction "GND_71_71") (pintype "passive"))
      (node (ref "I1") (pin "72") (pinfunction "GND_72_72") (pintype "passive"))
      (node (ref "I1") (pin "73") (pinfunction "GND_73_73") (pintype "passive"))
      (node (ref "J1") (pin "A1") (pinfunction "GND_A1") (pintype "power_in"))
      (node (ref "J1") (pin "A12") (pinfunction "GND_A12") (pintype "power_in"))
      (node (ref "J1") (pin "B1") (pinfunction "GND_B1") (pintype "power_in"))
      (node (ref "J1") (pin "B12") (pinfunction "GND_B12") (pintype "power_in"))
      (node (ref "J1") (pin "SH1") (pinfunction "SHIELD1_SH1") (pintype "power_in"))
      (node (ref "J1") (pin "SH2") (pinfunction "SHIELD2_SH2") (pintype "power_in"))
      (node (ref "J1") (pin "SH3") (pinfunction "SHIELD3_SH3") (pintype "power_in"))
      (node (ref "J1") (pin "SH4") (pinfunction "SHIELD4_SH4") (pintype "power_in"))
      (node (ref "J2") (pin "A1") (pinfunction "GND_A1") (pintype "power_in"))
      (node (ref "J2") (pin "A12") (pinfunction "GND_A12") (pintype "power_in"))
      (node (ref "J2") (pin "B1") (pinfunction "GND_B1") (pintype "power_in"))
      (node (ref "J2") (pin "B12") (pinfunction "GND_B12") (pintype "power_in"))
      (node (ref "J2") (pin "SH1") (pinfunction "SHIELD1_SH1") (pintype "power_in"))
      (node (ref "J2") (pin "SH2") (pinfunction "SHIELD2_SH2") (pintype "power_in"))
      (node (ref "J2") (pin "SH3") (pinfunction "SHIELD3_SH3") (pintype "power_in"))
      (node (ref "J2") (pin "SH4") (pinfunction "SHIELD4_SH4") (pintype "power_in"))
      (node (ref "P1") (pin "2") (pinfunction "2_2") (pintype "passive"))
      (node (ref "P1") (pin "24") (pinfunction "24_24") (pintype "passive"))
      (node (ref "P2") (pin "1") (pinfunction "1_1") (pintype "passive"))
      (node (ref "P2") (pin "23") (pinfunction "23_23") (pintype "passive"))
      (node (ref "R10") (pin "2") (pinfunction "2_2") (pintype "passive"))
      (node (ref "R4") (pin "2") (pinfunction "2_2") (pintype "passive"))
      (node (ref "R5") (pin "2") (pinfunction "2_2") (pintype "passive"))
      (node (ref "R6") (pin "2") (pinfunction "2_2") (pintype "passive"))
      (node (ref "R7") (pin "2") (pinfunction "2_2") (pintype "passive"))
      (node (ref "R8") (pin "2") (pinfunction "2_2") (pintype "passive"))
      (node (ref "SW1") (pin "3") (pinfunction "3_3") (pintype "passive"))
      (node (ref "SW1") (pin "4") (pinfunction "4_4") (pintype "passive"))
      (node (ref "SW2") (pin "3") (pinfunction "3_3") (pintype "passive"))
      (node (ref "SW2") (pin "4") (pinfunction "4_4") (pintype "passive"))
      (node (ref "U1") (pin "13") (pinfunction "GND_13") (pintype "power_in"))
      (node (ref "U1") (pin "21") (pinfunction "GND_21") (pintype "power_in"))
      (node (ref "U1") (pin "3") (pinfunction "GND_3") (pintype "power_in"))
      (node (ref "VR1") (pin "2") (pinfunction "GND_2") (pintype "passive"))
    )
    (net (code "60") (name "Net-(D7-A)") (class "Default")
      (node (ref "D7") (pin "2") (pinfunction "A_2") (pintype "passive"))
      (node (ref "R25") (pin "1") (pinfunction "1_1") (pintype "passive"))
    )
    (net (code "61") (name "Net-(D8-A)") (class "Default")
      (node (ref "D8") (pin "1") (pinfunction "A_1") (pintype "passive"))
      (node (ref "R26") (pin "1") (pinfunction "1_1") (pintype "passive"))
    )
    (net (code "62") (name "Net-(J1-CC1)") (class "Default")
      (node (ref "J1") (pin "A5") (pinfunction "CC1_A5") (pintype "bidirectional"))
      (node (ref "R4") (pin "1") (pinfunction "1_1") (pintype "passive"))
    )
    (net (code "63") (name "Net-(J1-CC2)") (class "Default")
      (node (ref "J1") (pin "B5") (pinfunction "CC2_B5") (pintype "bidirectional"))
      (node (ref "R5") (pin "1") (pinfunction "1_1") (pintype "passive"))
    )
    (net (code "64") (name "Net-(J2-CC1)") (class "Default")
      (node (ref "J2") (pin "A5") (pinfunction "CC1_A5") (pintype "bidirectional"))
      (node (ref "R6") (pin "1") (pinfunction "1_1") (pintype "passive"))
    )
    (net (code "65") (name "Net-(J2-CC2)") (class "Default")
      (node (ref "J2") (pin "B5") (pinfunction "CC2_B5") (pintype "bidirectional"))
      (node (ref "R7") (pin "1") (pinfunction "1_1") (pintype "passive"))
    )
    (net (code "66") (name "Net-(Q1-B)") (class "Default")
      (node (ref "Q1") (pin "2") (pinfunction "B_2") (pintype "passive"))
      (node (ref "R23") (pin "1") (pinfunction "1_1") (pintype "passive"))
    )
    (net (code "67") (name "Net-(Q2-B)") (class "Default")
      (node (ref "Q2") (pin "2") (pinfunction "B_2") (pintype "passive"))
      (node (ref "R24") (pin "1") (pinfunction "1_1") (pintype "passive"))
    )
    (net (code "68") (name "Net-(U1-3V3OUT)") (class "Default")
      (node (ref "C11") (pin "2") (pinfunction "2_2") (pintype "passive"))
      (node (ref "C12") (pin "2") (pinfunction "2_2") (pintype "passive"))
      (node (ref "R13") (pin "2") (pinfunction "2_2") (pintype "passive"))
      (node (ref "R14") (pin "1") (pinfunction "1_1") (pintype "passive"))
      (node (ref "U1") (pin "10") (pinfunction "3V3OUT_10") (pintype "passive"))
      (node (ref "U1") (pin "20") (pinfunction "VCCIO_20") (pintype "power_in"))
    )
    (net (code "69") (name "Net-(U1-CBUS0)") (class "Default")
      (node (ref "R8") (pin "1") (pinfunction "1_1") (pintype "passive"))
      (node (ref "U1") (pin "15") (pinfunction "CBUS0_15") (pintype "bidirectional"))
    )
    (net (code "70") (name "Net-(U1-CBUS3)") (class "Default")
      (node (ref "R10") (pin "1") (pinfunction "1_1") (pintype "passive"))
      (node (ref "R9") (pin "1") (pinfunction "1_1") (pintype "passive"))
      (node (ref "U1") (pin "16") (pinfunction "CBUS3_16") (pintype "bidirectional"))
    )
    (net (code "71") (name "Net-(U1-RESET#)") (class "Default")
      (node (ref "C10") (pin "2") (pinfunction "2_2") (pintype "passive"))
      (node (ref "R13") (pin "1") (pinfunction "1_1") (pintype "passive"))
      (node (ref "U1") (pin "11") (pinfunction "RESET#_11") (pintype "input"))
    )
    (net (code "72") (name "Net-(U1-USBDM)") (class "Default")
      (node (ref "R12") (pin "1") (pinfunction "1_1") (pintype "passive"))
      (node (ref "U1") (pin "9") (pinfunction "USBDM_9") (pintype "bidirectional"))
    )
    (net (code "73") (name "Net-(U1-USBDP)") (class "Default")
      (node (ref "R11") (pin "1") (pinfunction "1_1") (pintype "passive"))
      (node (ref "U1") (pin "8") (pinfunction "USBDP_8") (pintype "bidirectional"))
    )
    (net (code "74") (name "unconnected-(J1-SBU1-PadA8)") (class "Default")
      (node (ref "J1") (pin "A8") (pinfunction "SBU1_A8") (pintype "bidirectional+no_connect"))
    )
    (net (code "75") (name "unconnected-(J1-SBU2-PadB8)") (class "Default")
      (node (ref "J1") (pin "B8") (pinfunction "SBU2_B8") (pintype "bidirectional+no_connect"))
    )
    (net (code "76") (name "unconnected-(J2-SBU1-PadA8)") (class "Default")
      (node (ref "J2") (pin "A8") (pinfunction "SBU1_A8") (pintype "bidirectional+no_connect"))
    )
    (net (code "77") (name "unconnected-(J2-SBU2-PadB8)") (class "Default")
      (node (ref "J2") (pin "B8") (pinfunction "SBU2_B8") (pintype "bidirectional+no_connect"))
    )
    (net (code "78") (name "unconnected-(P2-Pad24)") (class "Default")
      (node (ref "P2") (pin "24") (pinfunction "24_24") (pintype "passive+no_connect"))
    )
    (net (code "79") (name "unconnected-(U1-CBUS1-Pad14)") (class "Default")
      (node (ref "U1") (pin "14") (pinfunction "CBUS1_14") (pintype "bidirectional+no_connect"))
    )
    (net (code "80") (name "unconnected-(U1-CBUS2-Pad7)") (class "Default")
      (node (ref "U1") (pin "7") (pinfunction "CBUS2_7") (pintype "bidirectional+no_connect"))
    )
    (net (code "81") (name "unconnected-(U1-CTS#-Pad6)") (class "Default")
      (node (ref "U1") (pin "6") (pinfunction "CTS#_6") (pintype "input+no_connect"))
    )
    (net (code "82") (name "unconnected-(U1-DCD#-Pad5)") (class "Default")
      (node (ref "U1") (pin "5") (pinfunction "DCD#_5") (pintype "input+no_connect"))
    )
    (net (code "83") (name "unconnected-(U1-DSR#-Pad4)") (class "Default")
      (node (ref "U1") (pin "4") (pinfunction "DSR#_4") (pintype "input+no_connect"))
    )
    (net (code "84") (name "unconnected-(U1-RI#-Pad2)") (class "Default")
      (node (ref "U1") (pin "2") (pinfunction "RI#_2") (pintype "input+no_connect"))
    )
  )
)
